# sht21_board.net
KiCad netlist of a schematic drawn in Altium Designer
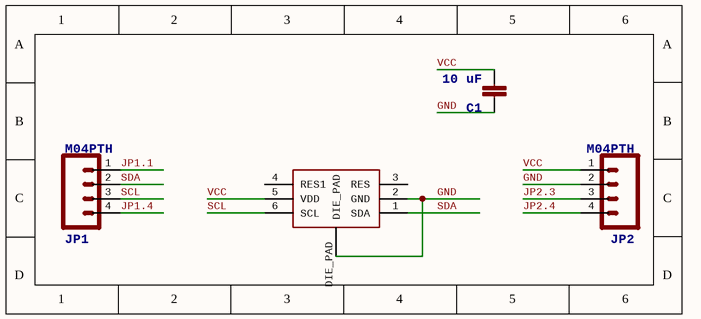
[diagram p0: sht21_board.SchDoc]

(export (version "E")
  (design (tool "Eeschema 10.0.6"))
  (components
    (comp (ref "C1")
      (value "10 uF")
      (footprint "0805")
      (description "<b>Capacitor</b>\nStandard 0603 ceramic capacitor, and 0.1\" leaded capacitor.")
      (libsource (lib "SparkFun-Passives") (part "CAP0805"))
    )
    (comp (ref "JP1")
      (value "M04PTH")
      (footprint "1X04")
      (libsource (lib "SparkFun-Connectors") (part "M04PTH"))
    )
    (comp (ref "JP2")
      (value "M04PTH")
      (footprint "1X04")
      (libsource (lib "SparkFun-Connectors") (part "M04PTH"))
    )
    (comp (ref "U$1") (value "SHT21") (footprint "SHT21_PADS") (libsource (lib "sensors") (part "SHT21")))
  )
  (nets
    (net (code "1") (name "/GND") (class "Default")
      (node (ref "C1") (pin "1") (pinfunction "1_1") (pintype "passive"))
      (node (ref "JP2") (pin "2") (pinfunction "2_2") (pintype "passive"))
      (node (ref "U$1") (pin "2") (pinfunction "GND_2") (pintype "passive"))
      (node (ref "U$1") (pin "DIE_PAD") (pinfunction "DIE_PAD_DIE_PAD") (pintype "passive"))
    )
    (net (code "2") (name "/JP1.1") (class "Default")
      (node (ref "JP1") (pin "1") (pinfunction "1_1") (pintype "passive"))
    )
    (net (code "3") (name "/JP1.4") (class "Default")
      (node (ref "JP1") (pin "4") (pinfunction "4_4") (pintype "passive"))
    )
    (net (code "4") (name "/JP2.3") (class "Default")
      (node (ref "JP2") (pin "3") (pinfunction "3_3") (pintype "passive"))
    )
    (net (code "5") (name "/JP2.4") (class "Default")
      (node (ref "JP2") (pin "4") (pinfunction "4_4") (pintype "passive"))
    )
    (net (code "6") (name "/SCL") (class "Default")
      (node (ref "JP1") (pin "3") (pinfunction "3_3") (pintype "passive"))
      (node (ref "U$1") (pin "6") (pinfunction "SCL_6") (pintype "passive"))
    )
    (net (code "7") (name "/SDA") (class "Default")
      (node (ref "JP1") (pin "2") (pinfunction "2_2") (pintype "passive"))
      (node (ref "U$1") (pin "1") (pinfunction "SDA_1") (pintype "passive"))
    )
    (net (code "8") (name "/VCC") (class "Default")
      (node (ref "C1") (pin "2") (pinfunction "2_2") (pintype "passive"))
      (node (ref "JP2") (pin "1") (pinfunction "1_1") (pintype "passive"))
      (node (ref "U$1") (pin "5") (pinfunction "VDD_5") (pintype "passive"))
    )
    (net (code "9") (name "unconnected-(U$1-RES-Pad3)") (class "Default")
      (node (ref "U$1") (pin "3") (pinfunction "RES_3") (pintype "passive"))
    )
    (net (code "10") (name "unconnected-(U$1-RES1-Pad4)") (class "Default")
      (node (ref "U$1") (pin "4") (pinfunction "RES1_4") (pintype "passive"))
    )
  )
)
